# Sheet2.net
KiCad netlist of a schematic drawn in Altium Designer
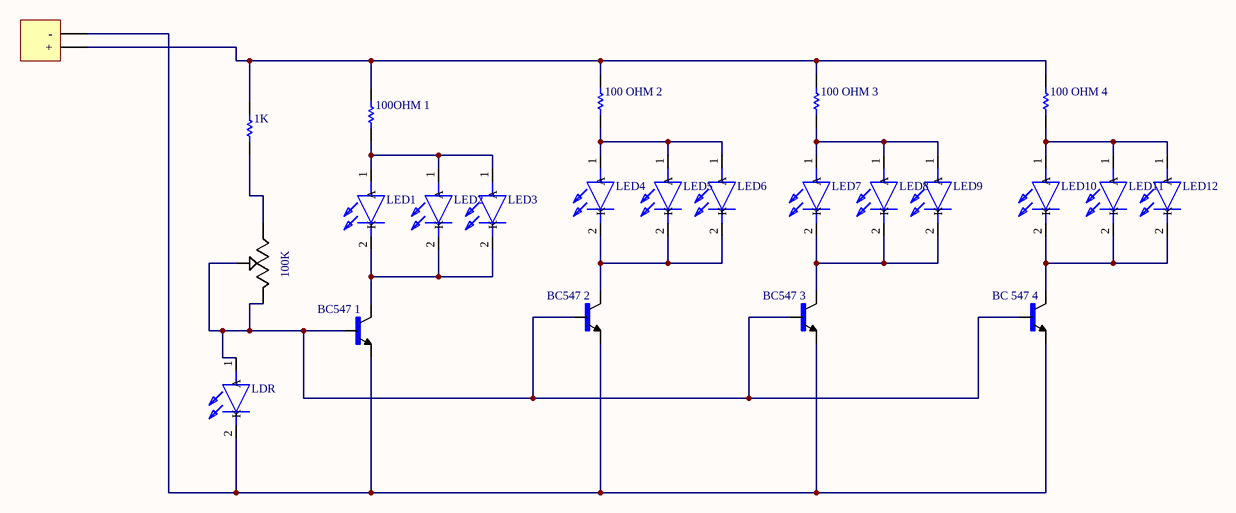
[diagram p0: Sheet2.SchDoc]

(export (version "E")
  (design (tool "Eeschema 10.0.6"))
  (components
    (comp (ref "1K")
      (value "Res1")
      (footprint "AXIAL-0.3")
      (description "Resistor")
      (fields (field (name "PUBLISHER") "Altium Limited"))
      (libsource (lib "Miscellaneous Devices") (part "Res1"))
    )
    (comp (ref "100 OHM 2")
      (value "Res1")
      (footprint "AXIAL-0.3")
      (description "Resistor")
      (fields (field (name "PUBLISHER") "Altium Limited"))
      (libsource (lib "Miscellaneous Devices") (part "Res1"))
    )
    (comp (ref "100 OHM 3")
      (value "Res1")
      (footprint "AXIAL-0.3")
      (description "Resistor")
      (fields (field (name "PUBLISHER") "Altium Limited"))
      (libsource (lib "Miscellaneous Devices") (part "Res1"))
    )
    (comp (ref "100 OHM 4")
      (value "Res1")
      (footprint "AXIAL-0.3")
      (description "Resistor")
      (fields (field (name "PUBLISHER") "Altium Limited"))
      (libsource (lib "Miscellaneous Devices") (part "Res1"))
    )
    (comp (ref "100K")
      (value "~")
      (footprint "*TRIM_EVN-D8AA03B14")
      (description "Trimmer; Carbon; Rest 10 Kilohms; PCB; 1 Turn; Pwr-Rtg 0.1 W; Linear; Top Adj; 6 mm SQ")
      (fields (field (name "MF") "Panasonic Electronic") (field (name "MP") "EVN-D8AA03B14"))
      (libsource (lib "EVN-D8AA03B14") (part "EVN-D8AA03B14"))
    )
    (comp (ref "100OHM 1")
      (value "Res1")
      (footprint "AXIAL-0.3")
      (description "Resistor")
      (fields (field (name "PUBLISHER") "Altium Limited"))
      (libsource (lib "Miscellaneous Devices") (part "Res1"))
    )
    (comp (ref "BC 547 4")
      (value "BC547*")
      (footprint "*TO92")
      (description "Transistor NPN BC547 PHILIPS miliampere=100 TO92")
      (fields (field (name "MP") "BC547") (field (name "MF") "ON Semiconductor"))
      (libsource (lib "BC547_") (part "BC547*"))
    )
    (comp (ref "BC547 1")
      (value "BC547*")
      (footprint "*TO92")
      (description "Transistor NPN BC547 PHILIPS miliampere=100 TO92")
      (fields (field (name "MP") "BC547") (field (name "MF") "ON Semiconductor"))
      (libsource (lib "BC547_") (part "BC547*"))
    )
    (comp (ref "BC547 2")
      (value "BC547*")
      (footprint "*TO92")
      (description "Transistor NPN BC547 PHILIPS miliampere=100 TO92")
      (fields (field (name "MP") "BC547") (field (name "MF") "ON Semiconductor"))
      (libsource (lib "BC547_") (part "BC547*"))
    )
    (comp (ref "BC547 3")
      (value "BC547*")
      (footprint "*TO92")
      (description "Transistor NPN BC547 PHILIPS miliampere=100 TO92")
      (fields (field (name "MP") "BC547") (field (name "MF") "ON Semiconductor"))
      (libsource (lib "BC547_") (part "BC547*"))
    )
    (comp (ref "HEADER")
      (value "Header 2")
      (footprint "HDR1X2")
      (description "Header, 2-Pin")
      (fields (field (name "PUBLISHER") "Altium Limited"))
      (libsource (lib "Miscellaneous Connectors") (part "Header 2"))
    )
    (comp (ref "LDR")
      (value "L-53GD")
      (footprint "SamacSys:L-53GD")
      (description "LED")
      (fields (field (name "RS PART NUMBER") "2286004A"))
      (libsource (lib "SamacSys") (part "L-53GD"))
    )
    (comp (ref "LED1")
      (value "L-53GD")
      (footprint "SamacSys:L-53GD")
      (description "LED")
      (fields (field (name "RS PART NUMBER") "2286004A"))
      (libsource (lib "SamacSys") (part "L-53GD"))
    )
    (comp (ref "LED2")
      (value "L-53GD")
      (footprint "SamacSys:L-53GD")
      (description "LED")
      (fields (field (name "RS PART NUMBER") "2286004A"))
      (libsource (lib "SamacSys") (part "L-53GD"))
    )
    (comp (ref "LED3")
      (value "L-53GD")
      (footprint "SamacSys:L-53GD")
      (description "LED")
      (fields (field (name "RS PART NUMBER") "2286004A"))
      (libsource (lib "SamacSys") (part "L-53GD"))
    )
    (comp (ref "LED4")
      (value "L-53GD")
      (footprint "SamacSys:L-53GD")
      (description "LED")
      (fields (field (name "RS PART NUMBER") "2286004A"))
      (libsource (lib "SamacSys") (part "L-53GD"))
    )
    (comp (ref "LED5")
      (value "L-53GD")
      (footprint "SamacSys:L-53GD")
      (description "LED")
      (fields (field (name "RS PART NUMBER") "2286004A"))
      (libsource (lib "SamacSys") (part "L-53GD"))
    )
    (comp (ref "LED6")
      (value "L-53GD")
      (footprint "SamacSys:L-53GD")
      (description "LED")
      (fields (field (name "RS PART NUMBER") "2286004A"))
      (libsource (lib "SamacSys") (part "L-53GD"))
    )
    (comp (ref "LED7")
      (value "L-53GD")
      (footprint "SamacSys:L-53GD")
      (description "LED")
      (fields (field (name "RS PART NUMBER") "2286004A"))
      (libsource (lib "SamacSys") (part "L-53GD"))
    )
    (comp (ref "LED8")
      (value "L-53GD")
      (footprint "SamacSys:L-53GD")
      (description "LED")
      (fields (field (name "RS PART NUMBER") "2286004A"))
      (libsource (lib "SamacSys") (part "L-53GD"))
    )
    (comp (ref "LED9")
      (value "L-53GD")
      (footprint "SamacSys:L-53GD")
      (description "LED")
      (fields (field (name "RS PART NUMBER") "2286004A"))
      (libsource (lib "SamacSys") (part "L-53GD"))
    )
    (comp (ref "LED10")
      (value "L-53GD")
      (footprint "SamacSys:L-53GD")
      (description "LED")
      (fields (field (name "RS PART NUMBER") "2286004A"))
      (libsource (lib "SamacSys") (part "L-53GD"))
    )
    (comp (ref "LED11")
      (value "L-53GD")
      (footprint "SamacSys:L-53GD")
      (description "LED")
      (fields (field (name "RS PART NUMBER") "2286004A"))
      (libsource (lib "SamacSys") (part "L-53GD"))
    )
    (comp (ref "LED12")
      (value "L-53GD")
      (footprint "SamacSys:L-53GD")
      (description "LED")
      (fields (field (name "RS PART NUMBER") "2286004A"))
      (libsource (lib "SamacSys") (part "L-53GD"))
    )
  )
  (nets
    (net (code "1") (name "Net-(100K-Pad1)") (class "Default")
      (node (ref "100K") (pin "1") (pinfunction "1_1") (pintype "passive"))
      (node (ref "1K") (pin "1") (pinfunction "1_1") (pintype "passive"))
    )
    (net (code "2") (name "Net-(BC 547 4-B)") (class "Default")
      (node (ref "100K") (pin "2") (pinfunction "2_2") (pintype "passive"))
      (node (ref "100K") (pin "3") (pinfunction "3_3") (pintype "passive"))
      (node (ref "BC 547 4") (pin "2") (pinfunction "B_2") (pintype "passive"))
      (node (ref "BC547 1") (pin "2") (pinfunction "B_2") (pintype "passive"))
      (node (ref "BC547 2") (pin "2") (pinfunction "B_2") (pintype "passive"))
      (node (ref "BC547 3") (pin "2") (pinfunction "B_2") (pintype "passive"))
      (node (ref "LDR") (pin "1") (pinfunction "A_1") (pintype "passive"))
    )
    (net (code "3") (name "Net-(BC 547 4-C)") (class "Default")
      (node (ref "BC 547 4") (pin "1") (pinfunction "C_1") (pintype "passive"))
      (node (ref "LED10") (pin "2") (pinfunction "K_2") (pintype "passive"))
      (node (ref "LED11") (pin "2") (pinfunction "K_2") (pintype "passive"))
      (node (ref "LED12") (pin "2") (pinfunction "K_2") (pintype "passive"))
    )
    (net (code "4") (name "Net-(BC 547 4-E)") (class "Default")
      (node (ref "BC 547 4") (pin "3") (pinfunction "E_3") (pintype "passive"))
      (node (ref "BC547 1") (pin "3") (pinfunction "E_3") (pintype "passive"))
      (node (ref "BC547 2") (pin "3") (pinfunction "E_3") (pintype "passive"))
      (node (ref "BC547 3") (pin "3") (pinfunction "E_3") (pintype "passive"))
      (node (ref "HEADER") (pin "2") (pinfunction "-_2") (pintype "passive"))
      (node (ref "LDR") (pin "2") (pinfunction "K_2") (pintype "passive"))
    )
    (net (code "5") (name "Net-(BC547 1-C)") (class "Default")
      (node (ref "BC547 1") (pin "1") (pinfunction "C_1") (pintype "passive"))
      (node (ref "LED1") (pin "2") (pinfunction "K_2") (pintype "passive"))
      (node (ref "LED2") (pin "2") (pinfunction "K_2") (pintype "passive"))
      (node (ref "LED3") (pin "2") (pinfunction "K_2") (pintype "passive"))
    )
    (net (code "6") (name "Net-(BC547 2-C)") (class "Default")
      (node (ref "BC547 2") (pin "1") (pinfunction "C_1") (pintype "passive"))
      (node (ref "LED4") (pin "2") (pinfunction "K_2") (pintype "passive"))
      (node (ref "LED5") (pin "2") (pinfunction "K_2") (pintype "passive"))
      (node (ref "LED6") (pin "2") (pinfunction "K_2") (pintype "passive"))
    )
    (net (code "7") (name "Net-(BC547 3-C)") (class "Default")
      (node (ref "BC547 3") (pin "1") (pinfunction "C_1") (pintype "passive"))
      (node (ref "LED7") (pin "2") (pinfunction "K_2") (pintype "passive"))
      (node (ref "LED8") (pin "2") (pinfunction "K_2") (pintype "passive"))
      (node (ref "LED9") (pin "2") (pinfunction "K_2") (pintype "passive"))
    )
    (net (code "8") (name "Net-(HEADER-+)") (class "Default")
      (node (ref "100 OHM 2") (pin "2") (pinfunction "2_2") (pintype "passive"))
      (node (ref "100 OHM 3") (pin "2") (pinfunction "2_2") (pintype "passive"))
      (node (ref "100 OHM 4") (pin "2") (pinfunction "2_2") (pintype "passive"))
      (node (ref "100OHM 1") (pin "2") (pinfunction "2_2") (pintype "passive"))
      (node (ref "1K") (pin "2") (pinfunction "2_2") (pintype "passive"))
      (node (ref "HEADER") (pin "1") (pinfunction "+_1") (pintype "passive"))
    )
    (net (code "9") (name "Net-(LED1-A)") (class "Default")
      (node (ref "100OHM 1") (pin "1") (pinfunction "1_1") (pintype "passive"))
      (node (ref "LED1") (pin "1") (pinfunction "A_1") (pintype "passive"))
      (node (ref "LED2") (pin "1") (pinfunction "A_1") (pintype "passive"))
      (node (ref "LED3") (pin "1") (pinfunction "A_1") (pintype "passive"))
    )
    (net (code "10") (name "Net-(LED4-A)") (class "Default")
      (node (ref "100 OHM 2") (pin "1") (pinfunction "1_1") (pintype "passive"))
      (node (ref "LED4") (pin "1") (pinfunction "A_1") (pintype "passive"))
      (node (ref "LED5") (pin "1") (pinfunction "A_1") (pintype "passive"))
      (node (ref "LED6") (pin "1") (pinfunction "A_1") (pintype "passive"))
    )
    (net (code "11") (name "Net-(LED7-A)") (class "Default")
      (node (ref "100 OHM 3") (pin "1") (pinfunction "1_1") (pintype "passive"))
      (node (ref "LED7") (pin "1") (pinfunction "A_1") (pintype "passive"))
      (node (ref "LED8") (pin "1") (pinfunction "A_1") (pintype "passive"))
      (node (ref "LED9") (pin "1") (pinfunction "A_1") (pintype "passive"))
    )
    (net (code "12") (name "Net-(LED10-A)") (class "Default")
      (node (ref "100 OHM 4") (pin "1") (pinfunction "1_1") (pintype "passive"))
      (node (ref "LED10") (pin "1") (pinfunction "A_1") (pintype "passive"))
      (node (ref "LED11") (pin "1") (pinfunction "A_1") (pintype "passive"))
      (node (ref "LED12") (pin "1") (pinfunction "A_1") (pintype "passive"))
    )
  )
)
